# uc4h_tfmini_v0201.net
KiCad netlist of a schematic drawn in EAGLE
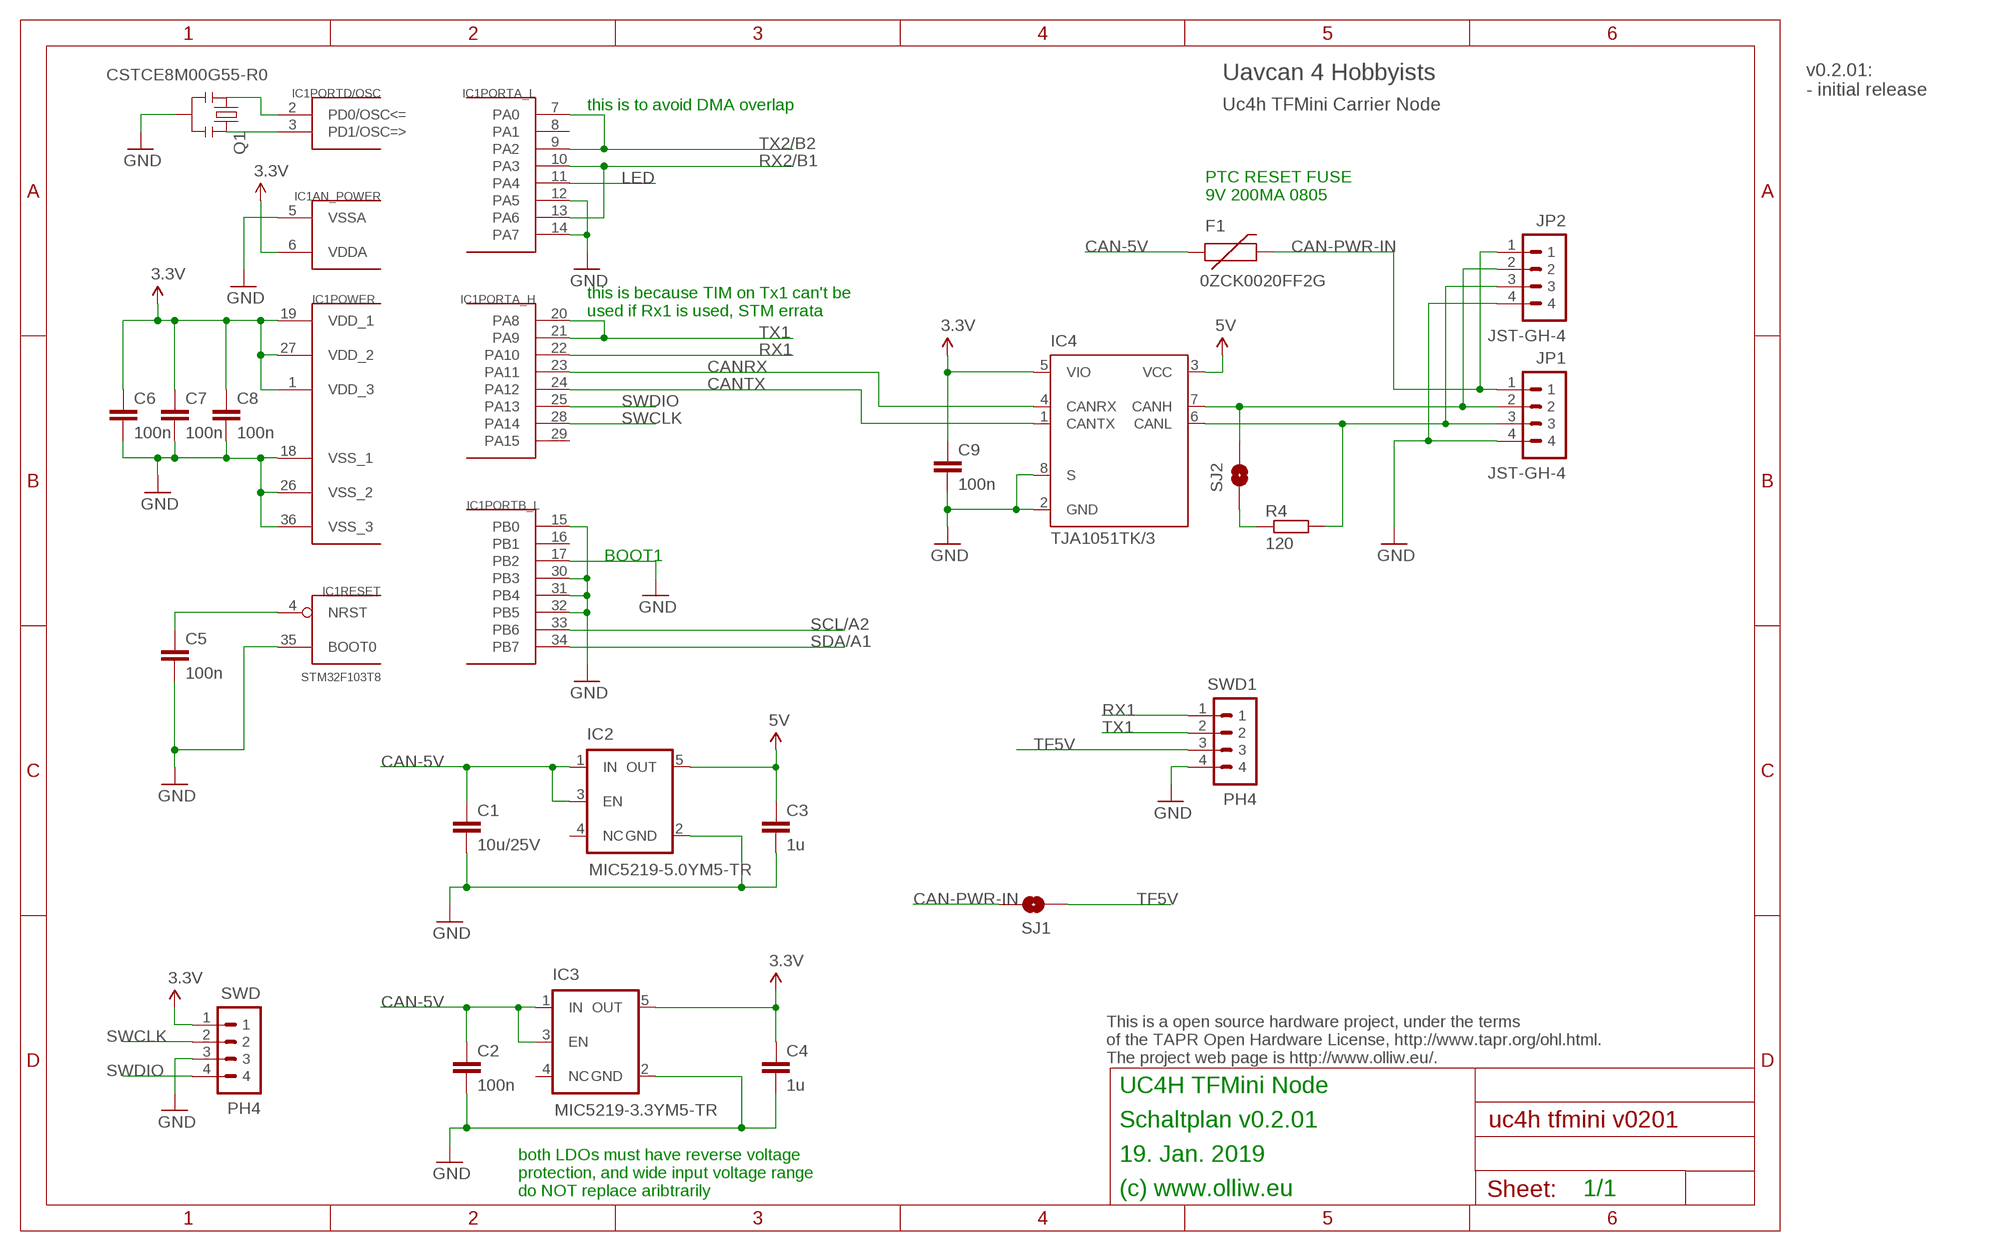
[diagram p0: schematic, sheet 1]

(export (version "E")
  (design (tool "Eeschema 10.0.6"))
  (components
    (comp (ref "C1")
      (value "10u/25V")
      (footprint "eagle-import:C1206")
      (libsource (lib "eagle-import") (part "C-EUC1206"))
    )
    (comp (ref "C2")
      (value "100n")
      (footprint "eagle-import:C0603K")
      (libsource (lib "eagle-import") (part "C-EUC0603K"))
    )
    (comp (ref "C3")
      (value "1u")
      (footprint "eagle-import:C0603K")
      (libsource (lib "eagle-import") (part "C-EUC0603K"))
    )
    (comp (ref "C4")
      (value "1u")
      (footprint "eagle-import:C0603K")
      (libsource (lib "eagle-import") (part "C-EUC0603K"))
    )
    (comp (ref "C5")
      (value "100n")
      (footprint "eagle-import:C0603K")
      (libsource (lib "eagle-import") (part "C-EUC0603K"))
    )
    (comp (ref "C6")
      (value "100n")
      (footprint "eagle-import:C0603K")
      (libsource (lib "eagle-import") (part "C-EUC0603K"))
    )
    (comp (ref "C7")
      (value "100n")
      (footprint "eagle-import:C0603K")
      (libsource (lib "eagle-import") (part "C-EUC0603K"))
    )
    (comp (ref "C8")
      (value "100n")
      (footprint "eagle-import:C0603K")
      (libsource (lib "eagle-import") (part "C-EUC0603K"))
    )
    (comp (ref "C9")
      (value "100n")
      (footprint "eagle-import:C0603K")
      (libsource (lib "eagle-import") (part "C-EUC0603K"))
    )
    (comp (ref "F1")
      (value "0ZCK0020FF2G")
      (footprint "eagle-import:FUSE-0805")
      (libsource (lib "eagle-import") (part "FUSE-PTCFUSE-0805"))
    )
    (comp (ref "IC1")
      (value "STM32F103T8")
      (footprint "eagle-import:VFQFPN36")
      (libsource (lib "eagle-import") (part "STM32F10XTXU6"))
    )
    (comp (ref "IC2")
      (value "MIC5219-5.0YM5-TR")
      (footprint "eagle-import:SOT23-5")
      (libsource (lib "eagle-import") (part "V_REG_TPS76433SOT23-5"))
    )
    (comp (ref "IC3")
      (value "MIC5219-3.3YM5-TR")
      (footprint "eagle-import:SOT23-5")
      (libsource (lib "eagle-import") (part "V_REG_TPS76433SOT23-5"))
    )
    (comp (ref "IC4")
      (value "TJA1051TK/3")
      (footprint "eagle-import:HVSON8")
      (libsource (lib "eagle-import") (part "TJA1051TK/3"))
    )
    (comp (ref "JP1")
      (value "JST-GH-4")
      (footprint "eagle-import:SM04B-GHS-TB")
      (libsource (lib "eagle-import") (part "JST-GH-4"))
    )
    (comp (ref "JP2")
      (value "JST-GH-4")
      (footprint "eagle-import:SM04B-GHS-TB")
      (libsource (lib "eagle-import") (part "JST-GH-4"))
    )
    (comp (ref "Q1")
      (value "CSTCE8M00G55-R0")
      (footprint "eagle-import:RESONATOR-SMD")
      (libsource (lib "eagle-import") (part "RESONATORSMD"))
    )
    (comp (ref "R4")
      (value "120")
      (footprint "eagle-import:R0603")
      (libsource (lib "eagle-import") (part "R-EU_R0603"))
    )
    (comp (ref "SJ1")
      (value "SOLDERJUMPERNO")
      (footprint "eagle-import:SJ_2S-NO")
      (libsource (lib "eagle-import") (part "SOLDERJUMPERNO"))
    )
    (comp (ref "SJ2")
      (value "SOLDERJUMPERNO")
      (footprint "eagle-import:SJ_2S-NO")
      (libsource (lib "eagle-import") (part "SOLDERJUMPERNO"))
    )
    (comp (ref "SWD")
      (value "PH4")
      (footprint "eagle-import:4X1_1P27_OCT_BILEX")
      (libsource (lib "eagle-import") (part "P4X1_1P27-OCT_BILEX"))
    )
    (comp (ref "SWD1")
      (value "PH4")
      (footprint "eagle-import:4X1_1P27_OCT_BILEX")
      (libsource (lib "eagle-import") (part "P4X1_1P27-OCT_BILEX"))
    )
  )
  (nets
    (net (code "1") (name "/CAN-5V") (class "Default")
      (node (ref "C1") (pin "1") (pinfunction "1_1") (pintype "passive"))
      (node (ref "C2") (pin "1") (pinfunction "1_1") (pintype "passive"))
      (node (ref "F1") (pin "1") (pinfunction "1_1") (pintype "bidirectional"))
      (node (ref "IC2") (pin "1") (pinfunction "IN_1") (pintype "power_in"))
      (node (ref "IC2") (pin "3") (pinfunction "EN_3") (pintype "input"))
      (node (ref "IC3") (pin "1") (pinfunction "IN_1") (pintype "power_in"))
      (node (ref "IC3") (pin "3") (pinfunction "EN_3") (pintype "input"))
    )
    (net (code "2") (name "/CAN-PWR-IN") (class "Default")
      (node (ref "F1") (pin "2") (pinfunction "2_2") (pintype "bidirectional"))
      (node (ref "JP1") (pin "1") (pinfunction "1_1") (pintype "passive"))
      (node (ref "JP2") (pin "1") (pinfunction "1_1") (pintype "passive"))
      (node (ref "SJ1") (pin "2") (pinfunction "2_2") (pintype "passive"))
    )
    (net (code "3") (name "/CANRX") (class "Default")
      (node (ref "IC1") (pin "23") (pinfunction "PA11_23") (pintype "bidirectional"))
      (node (ref "IC4") (pin "4") (pinfunction "CANRX_4") (pintype "output"))
    )
    (net (code "4") (name "/CANTX") (class "Default")
      (node (ref "IC1") (pin "24") (pinfunction "PA12_24") (pintype "bidirectional"))
      (node (ref "IC4") (pin "1") (pinfunction "CANTX_1") (pintype "input"))
    )
    (net (code "5") (name "/LED") (class "Default")
      (node (ref "IC1") (pin "11") (pinfunction "PA4_11") (pintype "bidirectional"))
    )
    (net (code "6") (name "/RX1") (class "Default")
      (node (ref "IC1") (pin "22") (pinfunction "PA10_22") (pintype "bidirectional"))
      (node (ref "SWD1") (pin "1") (pinfunction "1_1") (pintype "passive"))
    )
    (net (code "7") (name "/RX2{slash}B1") (class "Default")
      (node (ref "IC1") (pin "10") (pinfunction "PA3_10") (pintype "bidirectional"))
      (node (ref "IC1") (pin "13") (pinfunction "PA6_13") (pintype "bidirectional"))
    )
    (net (code "8") (name "/SCL{slash}A2") (class "Default")
      (node (ref "IC1") (pin "33") (pinfunction "PB6_33") (pintype "bidirectional"))
    )
    (net (code "9") (name "/SDA{slash}A1") (class "Default")
      (node (ref "IC1") (pin "34") (pinfunction "PB7_34") (pintype "bidirectional"))
    )
    (net (code "10") (name "/SWCLK") (class "Default")
      (node (ref "IC1") (pin "28") (pinfunction "PA14_28") (pintype "bidirectional"))
      (node (ref "SWD") (pin "2") (pinfunction "2_2") (pintype "passive"))
    )
    (net (code "11") (name "/SWDIO") (class "Default")
      (node (ref "IC1") (pin "25") (pinfunction "PA13_25") (pintype "bidirectional"))
      (node (ref "SWD") (pin "4") (pinfunction "4_4") (pintype "passive"))
    )
    (net (code "12") (name "/TF5V") (class "Default")
      (node (ref "SJ1") (pin "1") (pinfunction "1_1") (pintype "passive"))
      (node (ref "SWD1") (pin "3") (pinfunction "3_3") (pintype "passive"))
    )
    (net (code "13") (name "/TX1") (class "Default")
      (node (ref "IC1") (pin "20") (pinfunction "PA8_20") (pintype "bidirectional"))
      (node (ref "IC1") (pin "21") (pinfunction "PA9_21") (pintype "bidirectional"))
      (node (ref "SWD1") (pin "2") (pinfunction "2_2") (pintype "passive"))
    )
    (net (code "14") (name "/TX2{slash}B2") (class "Default")
      (node (ref "IC1") (pin "7") (pinfunction "PA0_7") (pintype "bidirectional"))
      (node (ref "IC1") (pin "9") (pinfunction "PA2_9") (pintype "bidirectional"))
    )
    (net (code "15") (name "3.3V") (class "Default")
      (node (ref "C4") (pin "1") (pinfunction "1_1") (pintype "passive"))
      (node (ref "C6") (pin "1") (pinfunction "1_1") (pintype "passive"))
      (node (ref "C7") (pin "1") (pinfunction "1_1") (pintype "passive"))
      (node (ref "C8") (pin "1") (pinfunction "1_1") (pintype "passive"))
      (node (ref "C9") (pin "1") (pinfunction "1_1") (pintype "passive"))
      (node (ref "IC1") (pin "1") (pinfunction "VDD_3_1") (pintype "power_in"))
      (node (ref "IC1") (pin "19") (pinfunction "VDD_1_19") (pintype "power_in"))
      (node (ref "IC1") (pin "27") (pinfunction "VDD_2_27") (pintype "power_in"))
      (node (ref "IC1") (pin "6") (pinfunction "VDDA_6") (pintype "power_in"))
      (node (ref "IC3") (pin "5") (pinfunction "OUT_5") (pintype "output"))
      (node (ref "IC4") (pin "5") (pinfunction "VIO_5") (pintype "power_in"))
      (node (ref "SWD") (pin "1") (pinfunction "1_1") (pintype "passive"))
    )
    (net (code "16") (name "5V") (class "Default")
      (node (ref "C3") (pin "1") (pinfunction "1_1") (pintype "passive"))
      (node (ref "IC2") (pin "5") (pinfunction "OUT_5") (pintype "output"))
      (node (ref "IC4") (pin "3") (pinfunction "VCC_3") (pintype "power_in"))
    )
    (net (code "17") (name "GND") (class "Default")
      (node (ref "C1") (pin "2") (pinfunction "2_2") (pintype "passive"))
      (node (ref "C2") (pin "2") (pinfunction "2_2") (pintype "passive"))
      (node (ref "C3") (pin "2") (pinfunction "2_2") (pintype "passive"))
      (node (ref "C4") (pin "2") (pinfunction "2_2") (pintype "passive"))
      (node (ref "C5") (pin "2") (pinfunction "2_2") (pintype "passive"))
      (node (ref "C6") (pin "2") (pinfunction "2_2") (pintype "passive"))
      (node (ref "C7") (pin "2") (pinfunction "2_2") (pintype "passive"))
      (node (ref "C8") (pin "2") (pinfunction "2_2") (pintype "passive"))
      (node (ref "C9") (pin "2") (pinfunction "2_2") (pintype "passive"))
      (node (ref "IC1") (pin "12") (pinfunction "PA5_12") (pintype "bidirectional"))
      (node (ref "IC1") (pin "14") (pinfunction "PA7_14") (pintype "bidirectional"))
      (node (ref "IC1") (pin "15") (pinfunction "PB0_15") (pintype "bidirectional"))
      (node (ref "IC1") (pin "17") (pinfunction "PB2_17") (pintype "bidirectional"))
      (node (ref "IC1") (pin "18") (pinfunction "VSS_1_18") (pintype "power_in"))
      (node (ref "IC1") (pin "26") (pinfunction "VSS_2_26") (pintype "power_in"))
      (node (ref "IC1") (pin "30") (pinfunction "PB3_30") (pintype "bidirectional"))
      (node (ref "IC1") (pin "31") (pinfunction "PB4_31") (pintype "bidirectional"))
      (node (ref "IC1") (pin "32") (pinfunction "PB5_32") (pintype "bidirectional"))
      (node (ref "IC1") (pin "35") (pinfunction "BOOT0_35") (pintype "input"))
      (node (ref "IC1") (pin "36") (pinfunction "VSS_3_36") (pintype "power_in"))
      (node (ref "IC1") (pin "5") (pinfunction "VSSA_5") (pintype "power_in"))
      (node (ref "IC2") (pin "2") (pinfunction "GND_2") (pintype "power_in"))
      (node (ref "IC3") (pin "2") (pinfunction "GND_2") (pintype "power_in"))
      (node (ref "IC4") (pin "2") (pinfunction "GND_2") (pintype "power_in"))
      (node (ref "IC4") (pin "8") (pinfunction "S_8") (pintype "input"))
      (node (ref "JP1") (pin "4") (pinfunction "4_4") (pintype "passive"))
      (node (ref "JP2") (pin "4") (pinfunction "4_4") (pintype "passive"))
      (node (ref "Q1") (pin "2") (pinfunction "2_2") (pintype "passive"))
      (node (ref "SWD") (pin "3") (pinfunction "3_3") (pintype "passive"))
      (node (ref "SWD1") (pin "4") (pinfunction "4_4") (pintype "passive"))
    )
    (net (code "18") (name "Net-(IC1E-PD0{slash}OSC<=)") (class "Default")
      (node (ref "IC1") (pin "2") (pinfunction "PD0/OSC<=_2") (pintype "bidirectional"))
      (node (ref "Q1") (pin "1") (pinfunction "1_1") (pintype "passive"))
    )
    (net (code "19") (name "Net-(IC1E-PD1{slash}OSC=>)") (class "Default")
      (node (ref "IC1") (pin "3") (pinfunction "PD1/OSC=>_3") (pintype "bidirectional"))
      (node (ref "Q1") (pin "3") (pinfunction "3_3") (pintype "passive"))
    )
    (net (code "20") (name "Net-(IC1G-NRST)") (class "Default")
      (node (ref "C5") (pin "1") (pinfunction "1_1") (pintype "passive"))
      (node (ref "IC1") (pin "4") (pinfunction "NRST_4") (pintype "input"))
    )
    (net (code "21") (name "Net-(IC4-CANH)") (class "Default")
      (node (ref "IC4") (pin "7") (pinfunction "CANH_7") (pintype "bidirectional"))
      (node (ref "JP1") (pin "2") (pinfunction "2_2") (pintype "passive"))
      (node (ref "JP2") (pin "2") (pinfunction "2_2") (pintype "passive"))
      (node (ref "SJ2") (pin "2") (pinfunction "2_2") (pintype "passive"))
    )
    (net (code "22") (name "Net-(IC4-CANL)") (class "Default")
      (node (ref "IC4") (pin "6") (pinfunction "CANL_6") (pintype "bidirectional"))
      (node (ref "JP1") (pin "3") (pinfunction "3_3") (pintype "passive"))
      (node (ref "JP2") (pin "3") (pinfunction "3_3") (pintype "passive"))
      (node (ref "R4") (pin "2") (pinfunction "2_2") (pintype "passive"))
    )
    (net (code "23") (name "Net-(R4-Pad1)") (class "Default")
      (node (ref "R4") (pin "1") (pinfunction "1_1") (pintype "passive"))
      (node (ref "SJ2") (pin "1") (pinfunction "1_1") (pintype "passive"))
    )
    (net (code "24") (name "unconnected-(IC1B-PA15-Pad29)") (class "Default")
      (node (ref "IC1") (pin "29") (pinfunction "PA15_29") (pintype "bidirectional"))
    )
    (net (code "25") (name "unconnected-(IC1C-PA1-Pad8)") (class "Default")
      (node (ref "IC1") (pin "8") (pinfunction "PA1_8") (pintype "bidirectional"))
    )
    (net (code "26") (name "unconnected-(IC1D-PB1-Pad16)") (class "Default")
      (node (ref "IC1") (pin "16") (pinfunction "PB1_16") (pintype "bidirectional"))
    )
    (net (code "27") (name "unconnected-(IC2-NC-Pad4)") (class "Default")
      (node (ref "IC2") (pin "4") (pinfunction "NC_4") (pintype "passive"))
    )
    (net (code "28") (name "unconnected-(IC3-NC-Pad4)") (class "Default")
      (node (ref "IC3") (pin "4") (pinfunction "NC_4") (pintype "passive"))
    )
  )
)
